# EIT_Recorder.net
KiCad netlist of a schematic drawn in EAGLE
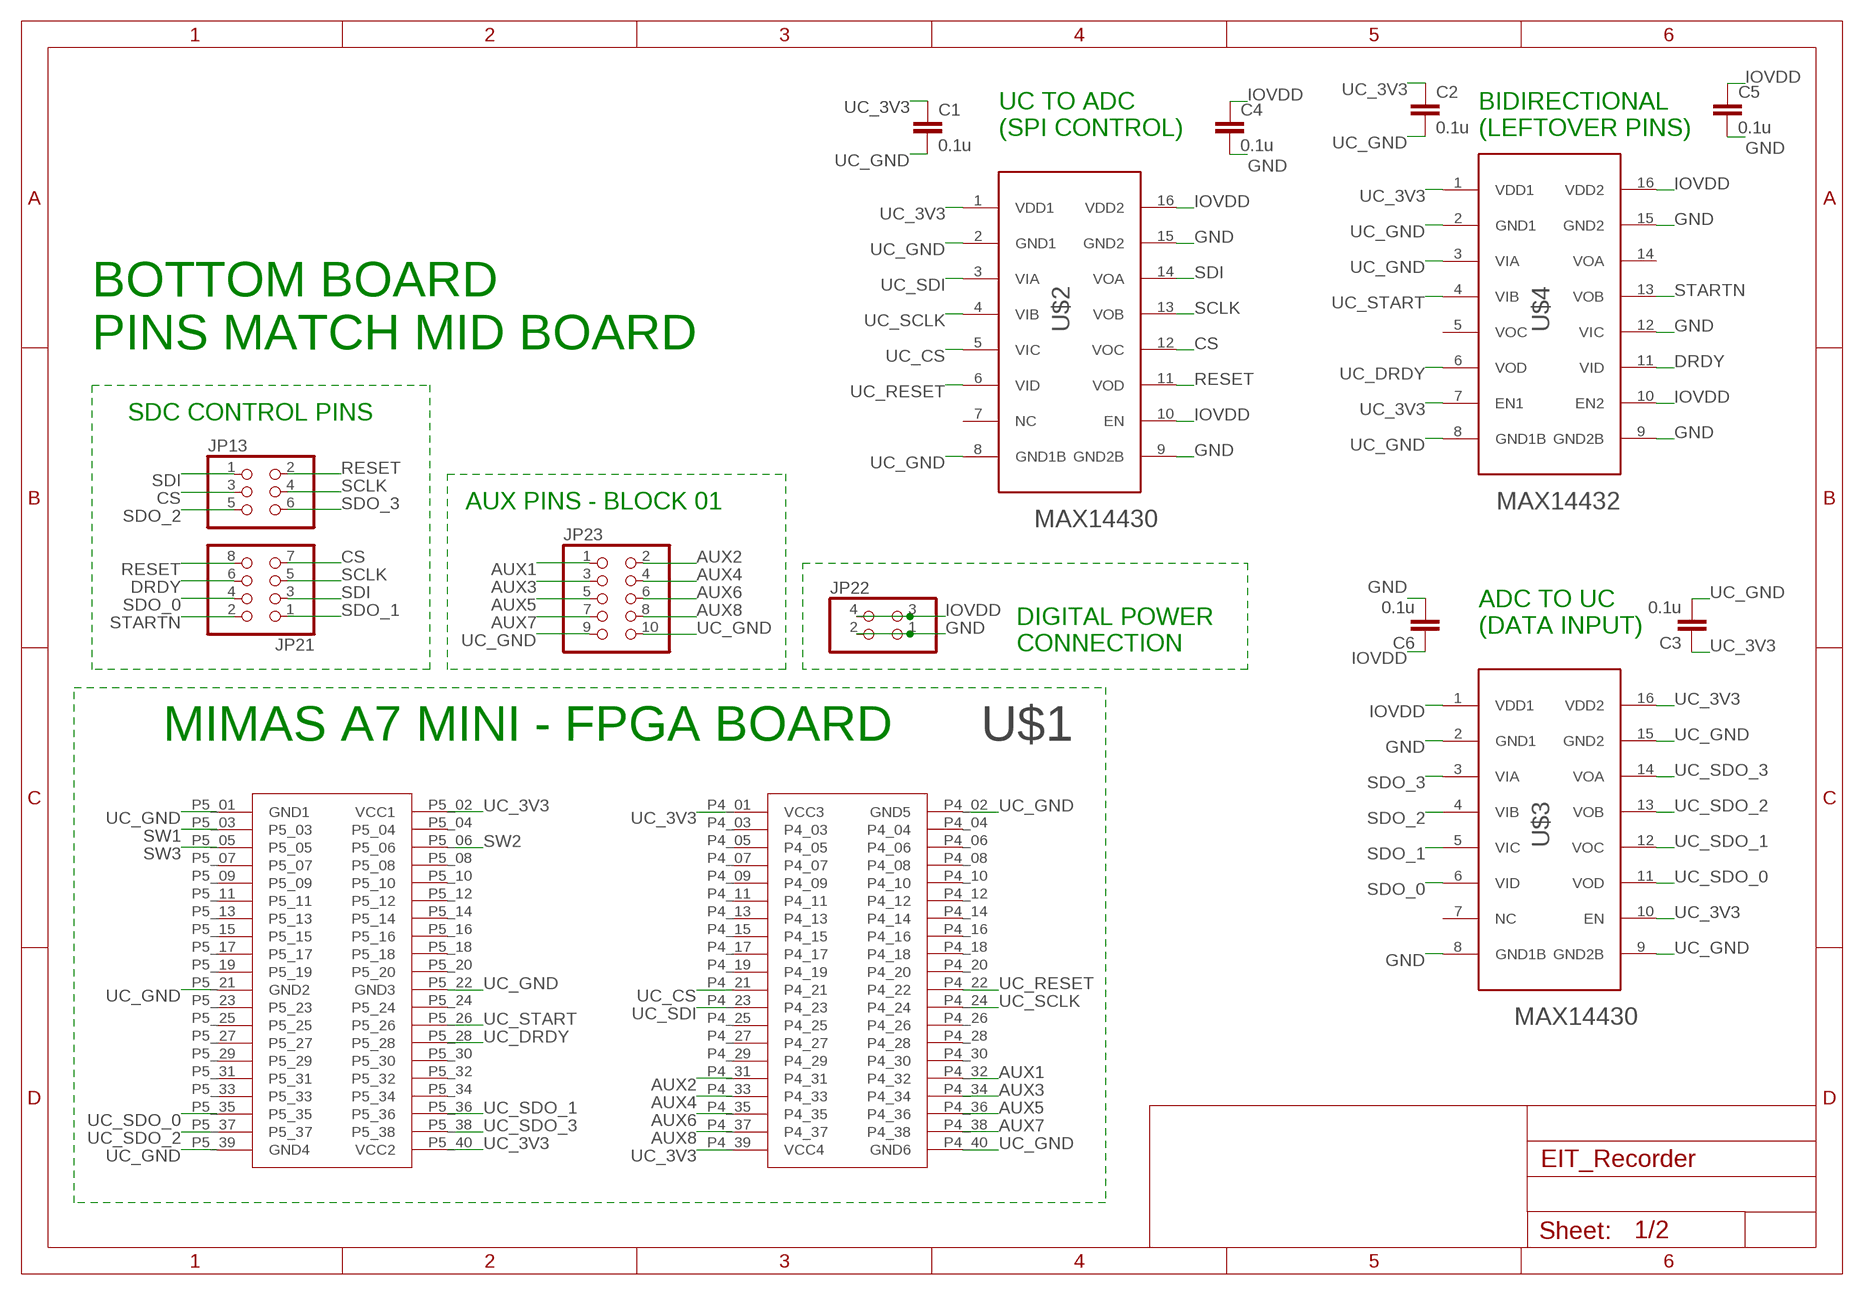
[diagram p0: schematic, sheet 1]
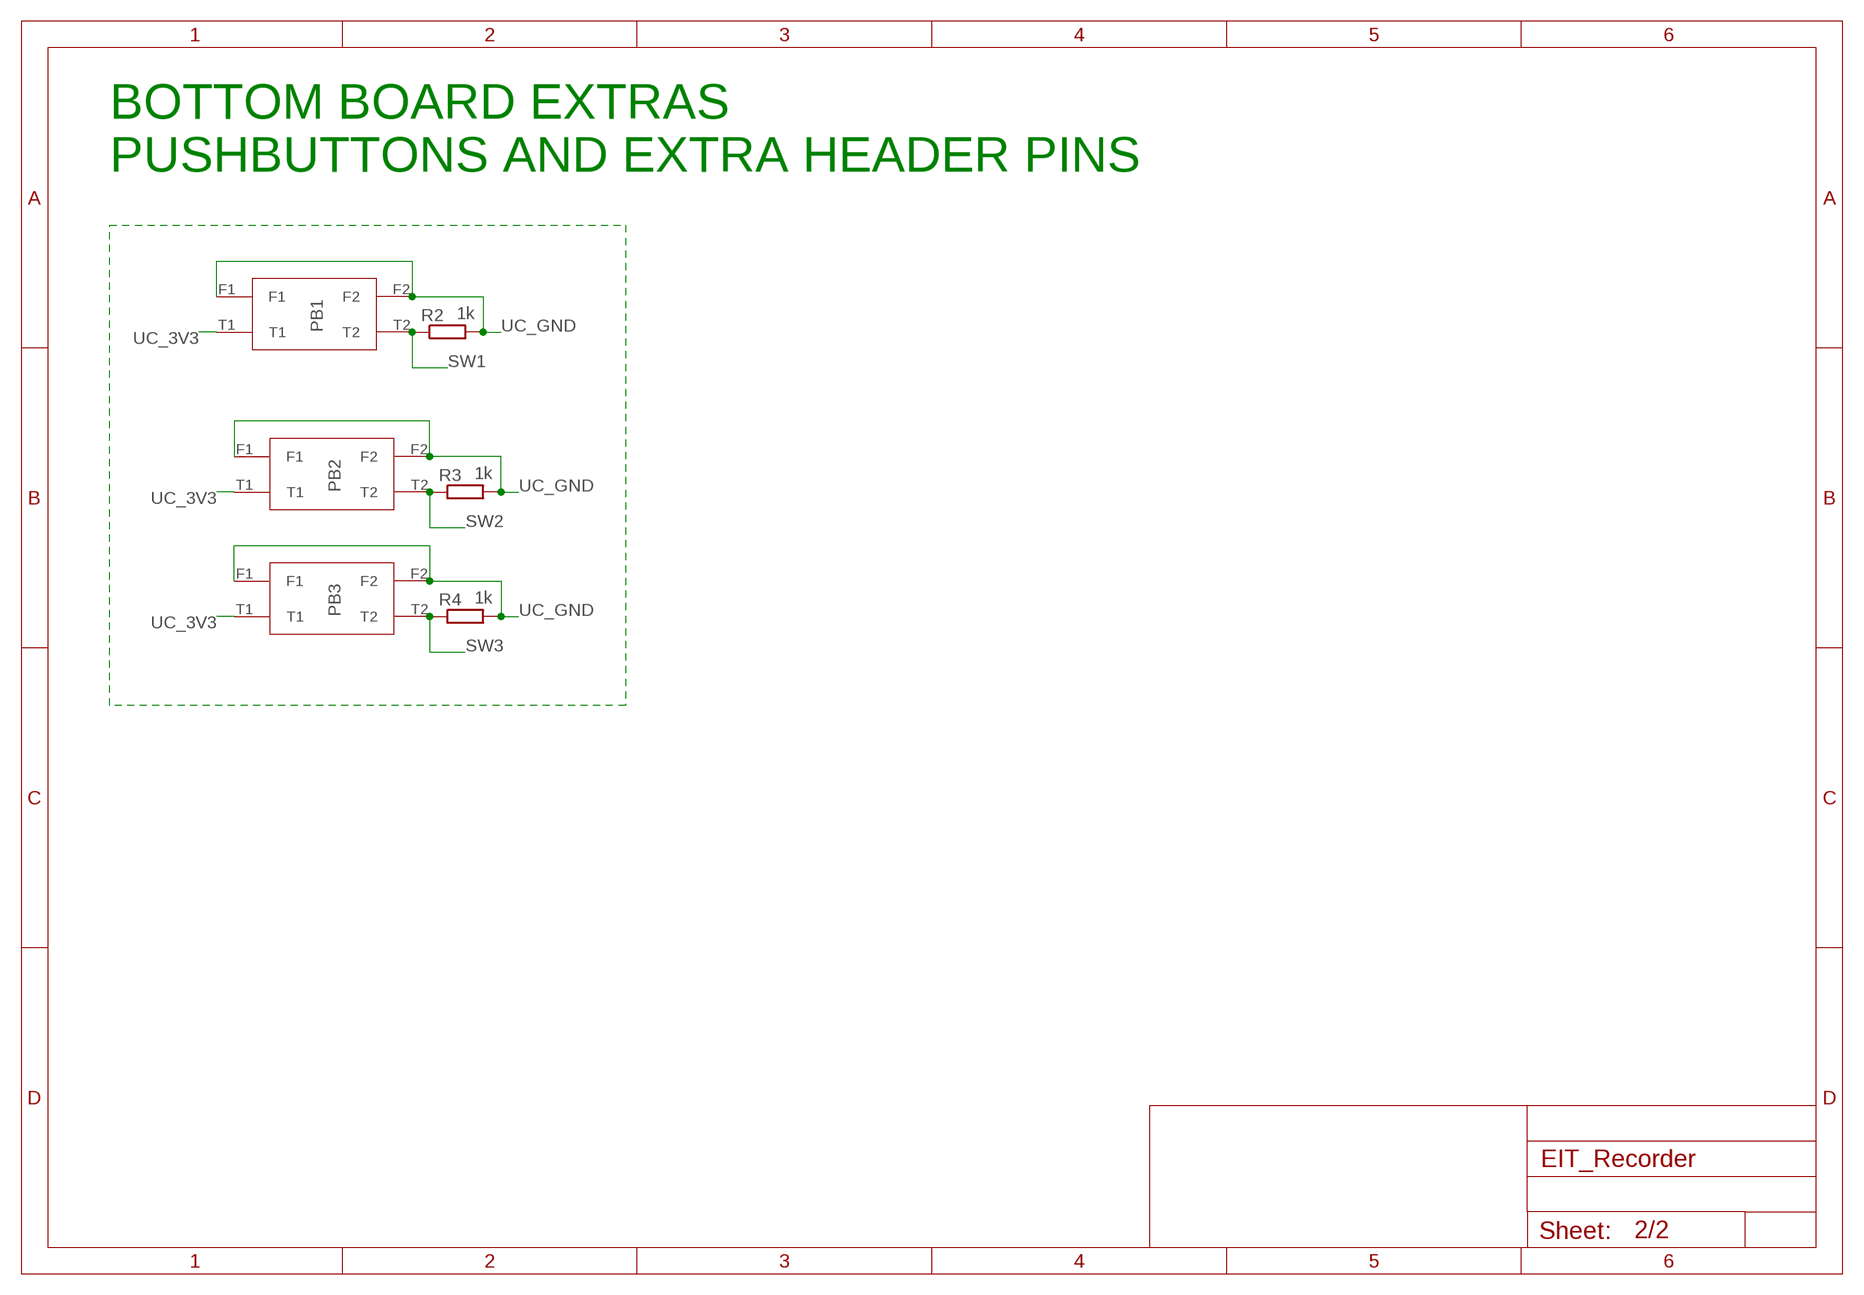
[diagram p1: schematic, sheet 2]

(export (version "E")
  (design (tool "Eeschema 10.0.6"))
  (components
    (comp (ref "PB1")
      (value "PUSHBUTTON_95C06B2RAT")
      (footprint "eagle-import:PUSHBUTTON_95C06B2RAT")
      (libsource (lib "eagle-import") (part "PUSHBUTTON_95C06B2RAT"))
    )
    (comp (ref "PB2")
      (value "PUSHBUTTON_95C06B2RAT")
      (footprint "eagle-import:PUSHBUTTON_95C06B2RAT")
      (libsource (lib "eagle-import") (part "PUSHBUTTON_95C06B2RAT"))
    )
    (comp (ref "PB3")
      (value "PUSHBUTTON_95C06B2RAT")
      (footprint "eagle-import:PUSHBUTTON_95C06B2RAT")
      (libsource (lib "eagle-import") (part "PUSHBUTTON_95C06B2RAT"))
    )
    (comp (ref "R2")
      (value "1k")
      (footprint "eagle-import:R0805")
      (libsource (lib "eagle-import") (part "R-EU_R0805"))
    )
    (comp (ref "R3")
      (value "1k")
      (footprint "eagle-import:R0805")
      (libsource (lib "eagle-import") (part "R-EU_R0805"))
    )
    (comp (ref "R4")
      (value "1k")
      (footprint "eagle-import:R0805")
      (libsource (lib "eagle-import") (part "R-EU_R0805"))
    )
    (comp (ref "C1")
      (value "0.1u")
      (footprint "eagle-import:C0805")
      (libsource (lib "eagle-import") (part "C-EUC0805"))
    )
    (comp (ref "C2")
      (value "0.1u")
      (footprint "eagle-import:C0805")
      (libsource (lib "eagle-import") (part "C-EUC0805"))
    )
    (comp (ref "C3")
      (value "0.1u")
      (footprint "eagle-import:C0805")
      (libsource (lib "eagle-import") (part "C-EUC0805"))
    )
    (comp (ref "C4")
      (value "0.1u")
      (footprint "eagle-import:C0805")
      (libsource (lib "eagle-import") (part "C-EUC0805"))
    )
    (comp (ref "C5")
      (value "0.1u")
      (footprint "eagle-import:C0805")
      (libsource (lib "eagle-import") (part "C-EUC0805"))
    )
    (comp (ref "C6")
      (value "0.1u")
      (footprint "eagle-import:C0805")
      (libsource (lib "eagle-import") (part "C-EUC0805"))
    )
    (comp (ref "JP13")
      (value "PINHD-2X3")
      (footprint "eagle-import:2X03")
      (libsource (lib "eagle-import") (part "PINHD-2X3"))
    )
    (comp (ref "JP21")
      (value "PINHD-2X4")
      (footprint "eagle-import:2X04")
      (libsource (lib "eagle-import") (part "PINHD-2X4"))
    )
    (comp (ref "JP22")
      (value "PINHD-2X2")
      (footprint "eagle-import:2X02")
      (libsource (lib "eagle-import") (part "PINHD-2X2"))
    )
    (comp (ref "JP23")
      (value "PINHD-2X5/90")
      (footprint "eagle-import:2X05_90")
      (libsource (lib "eagle-import") (part "PINHD-2X5/90"))
    )
    (comp (ref "U$1")
      (value "MIMAS_A7_MINI")
      (footprint "eagle-import:MIMAS_A7_MINI")
      (libsource (lib "eagle-import") (part "MIMAS_A7_MINI"))
    )
    (comp (ref "U$2")
      (value "MAX14430")
      (footprint "eagle-import:SOIC16_CUSTOM")
      (libsource (lib "eagle-import") (part "MAX14430"))
    )
    (comp (ref "U$3")
      (value "MAX14430")
      (footprint "eagle-import:SOIC16_CUSTOM")
      (libsource (lib "eagle-import") (part "MAX14430"))
    )
    (comp (ref "U$4")
      (value "MAX14432")
      (footprint "eagle-import:SOIC16_CUSTOM")
      (libsource (lib "eagle-import") (part "MAX14432"))
    )
  )
  (nets
    (net (code "1") (name "AUX1") (class "Default")
      (node (ref "JP23") (pin "1") (pinfunction "1_1") (pintype "passive"))
      (node (ref "U$1") (pin "P4_32") (pinfunction "P4_32_P4_32") (pintype "bidirectional"))
    )
    (net (code "2") (name "AUX2") (class "Default")
      (node (ref "JP23") (pin "2") (pinfunction "2_2") (pintype "passive"))
      (node (ref "U$1") (pin "P4_31") (pinfunction "P4_31_P4_31") (pintype "bidirectional"))
    )
    (net (code "3") (name "AUX3") (class "Default")
      (node (ref "JP23") (pin "3") (pinfunction "3_3") (pintype "passive"))
      (node (ref "U$1") (pin "P4_34") (pinfunction "P4_34_P4_34") (pintype "bidirectional"))
    )
    (net (code "4") (name "AUX4") (class "Default")
      (node (ref "JP23") (pin "4") (pinfunction "4_4") (pintype "passive"))
      (node (ref "U$1") (pin "P4_33") (pinfunction "P4_33_P4_33") (pintype "bidirectional"))
    )
    (net (code "5") (name "AUX5") (class "Default")
      (node (ref "JP23") (pin "5") (pinfunction "5_5") (pintype "passive"))
      (node (ref "U$1") (pin "P4_36") (pinfunction "P4_36_P4_36") (pintype "bidirectional"))
    )
    (net (code "6") (name "AUX6") (class "Default")
      (node (ref "JP23") (pin "6") (pinfunction "6_6") (pintype "passive"))
      (node (ref "U$1") (pin "P4_35") (pinfunction "P4_35_P4_35") (pintype "bidirectional"))
    )
    (net (code "7") (name "AUX7") (class "Default")
      (node (ref "JP23") (pin "7") (pinfunction "7_7") (pintype "passive"))
      (node (ref "U$1") (pin "P4_38") (pinfunction "P4_38_P4_38") (pintype "bidirectional"))
    )
    (net (code "8") (name "AUX8") (class "Default")
      (node (ref "JP23") (pin "8") (pinfunction "8_8") (pintype "passive"))
      (node (ref "U$1") (pin "P4_37") (pinfunction "P4_37_P4_37") (pintype "bidirectional"))
    )
    (net (code "9") (name "CS") (class "Default")
      (node (ref "JP13") (pin "3") (pinfunction "3_3") (pintype "passive"))
      (node (ref "JP21") (pin "7") (pinfunction "7_7") (pintype "passive"))
      (node (ref "U$2") (pin "12") (pinfunction "VOC_12") (pintype "output"))
    )
    (net (code "10") (name "DRDY") (class "Default")
      (node (ref "JP21") (pin "6") (pinfunction "6_6") (pintype "passive"))
      (node (ref "U$4") (pin "11") (pinfunction "VID_11") (pintype "input"))
    )
    (net (code "11") (name "GND") (class "Default")
      (node (ref "C4") (pin "2") (pinfunction "2_2") (pintype "passive"))
      (node (ref "C5") (pin "2") (pinfunction "2_2") (pintype "passive"))
      (node (ref "C6") (pin "2") (pinfunction "2_2") (pintype "passive"))
      (node (ref "JP22") (pin "1") (pinfunction "1_1") (pintype "passive"))
      (node (ref "JP22") (pin "2") (pinfunction "2_2") (pintype "passive"))
      (node (ref "U$2") (pin "15") (pinfunction "GND2_15") (pintype "power_in"))
      (node (ref "U$2") (pin "9") (pinfunction "GND2B_9") (pintype "power_in"))
      (node (ref "U$3") (pin "2") (pinfunction "GND1_2") (pintype "power_in"))
      (node (ref "U$3") (pin "8") (pinfunction "GND1B_8") (pintype "power_in"))
      (node (ref "U$4") (pin "12") (pinfunction "VIC_12") (pintype "input"))
      (node (ref "U$4") (pin "15") (pinfunction "GND2_15") (pintype "power_in"))
      (node (ref "U$4") (pin "9") (pinfunction "GND2B_9") (pintype "power_in"))
    )
    (net (code "12") (name "IOVDD") (class "Default")
      (node (ref "C4") (pin "1") (pinfunction "1_1") (pintype "passive"))
      (node (ref "C5") (pin "1") (pinfunction "1_1") (pintype "passive"))
      (node (ref "C6") (pin "1") (pinfunction "1_1") (pintype "passive"))
      (node (ref "JP22") (pin "3") (pinfunction "3_3") (pintype "passive"))
      (node (ref "JP22") (pin "4") (pinfunction "4_4") (pintype "passive"))
      (node (ref "U$2") (pin "10") (pinfunction "EN_10") (pintype "bidirectional"))
      (node (ref "U$2") (pin "16") (pinfunction "VDD2_16") (pintype "power_in"))
      (node (ref "U$3") (pin "1") (pinfunction "VDD1_1") (pintype "power_in"))
      (node (ref "U$4") (pin "10") (pinfunction "EN2_10") (pintype "bidirectional"))
      (node (ref "U$4") (pin "16") (pinfunction "VDD2_16") (pintype "power_in"))
    )
    (net (code "13") (name "RESET") (class "Default")
      (node (ref "JP13") (pin "2") (pinfunction "2_2") (pintype "passive"))
      (node (ref "JP21") (pin "8") (pinfunction "8_8") (pintype "passive"))
      (node (ref "U$2") (pin "11") (pinfunction "VOD_11") (pintype "output"))
    )
    (net (code "14") (name "SCLK") (class "Default")
      (node (ref "JP13") (pin "4") (pinfunction "4_4") (pintype "passive"))
      (node (ref "JP21") (pin "5") (pinfunction "5_5") (pintype "passive"))
      (node (ref "U$2") (pin "13") (pinfunction "VOB_13") (pintype "output"))
    )
    (net (code "15") (name "SDI") (class "Default")
      (node (ref "JP13") (pin "1") (pinfunction "1_1") (pintype "passive"))
      (node (ref "JP21") (pin "3") (pinfunction "3_3") (pintype "passive"))
      (node (ref "U$2") (pin "14") (pinfunction "VOA_14") (pintype "output"))
    )
    (net (code "16") (name "SDO_0") (class "Default")
      (node (ref "JP21") (pin "4") (pinfunction "4_4") (pintype "passive"))
      (node (ref "U$3") (pin "6") (pinfunction "VID_6") (pintype "input"))
    )
    (net (code "17") (name "SDO_1") (class "Default")
      (node (ref "JP21") (pin "1") (pinfunction "1_1") (pintype "passive"))
      (node (ref "U$3") (pin "5") (pinfunction "VIC_5") (pintype "input"))
    )
    (net (code "18") (name "SDO_2") (class "Default")
      (node (ref "JP13") (pin "5") (pinfunction "5_5") (pintype "passive"))
      (node (ref "U$3") (pin "4") (pinfunction "VIB_4") (pintype "input"))
    )
    (net (code "19") (name "SDO_3") (class "Default")
      (node (ref "JP13") (pin "6") (pinfunction "6_6") (pintype "passive"))
      (node (ref "U$3") (pin "3") (pinfunction "VIA_3") (pintype "input"))
    )
    (net (code "20") (name "STARTN") (class "Default")
      (node (ref "JP21") (pin "2") (pinfunction "2_2") (pintype "passive"))
      (node (ref "U$4") (pin "13") (pinfunction "VOB_13") (pintype "output"))
    )
    (net (code "21") (name "SW1") (class "Default")
      (node (ref "PB1") (pin "T2") (pinfunction "T2_T2") (pintype "bidirectional"))
      (node (ref "R2") (pin "1") (pinfunction "1_1") (pintype "passive"))
      (node (ref "U$1") (pin "P5_03") (pinfunction "P5_03_P5_03") (pintype "bidirectional"))
    )
    (net (code "22") (name "SW2") (class "Default")
      (node (ref "PB2") (pin "T2") (pinfunction "T2_T2") (pintype "bidirectional"))
      (node (ref "R3") (pin "1") (pinfunction "1_1") (pintype "passive"))
      (node (ref "U$1") (pin "P5_06") (pinfunction "P5_06_P5_06") (pintype "bidirectional"))
    )
    (net (code "23") (name "SW3") (class "Default")
      (node (ref "PB3") (pin "T2") (pinfunction "T2_T2") (pintype "bidirectional"))
      (node (ref "R4") (pin "1") (pinfunction "1_1") (pintype "passive"))
      (node (ref "U$1") (pin "P5_05") (pinfunction "P5_05_P5_05") (pintype "bidirectional"))
    )
    (net (code "24") (name "UC_3V3") (class "Default")
      (node (ref "C1") (pin "1") (pinfunction "1_1") (pintype "passive"))
      (node (ref "C2") (pin "1") (pinfunction "1_1") (pintype "passive"))
      (node (ref "C3") (pin "1") (pinfunction "1_1") (pintype "passive"))
      (node (ref "PB1") (pin "T1") (pinfunction "T1_T1") (pintype "bidirectional"))
      (node (ref "PB2") (pin "T1") (pinfunction "T1_T1") (pintype "bidirectional"))
      (node (ref "PB3") (pin "T1") (pinfunction "T1_T1") (pintype "bidirectional"))
      (node (ref "U$1") (pin "P4_01") (pinfunction "VCC3_P4_01") (pintype "power_in"))
      (node (ref "U$1") (pin "P4_39") (pinfunction "VCC4_P4_39") (pintype "power_in"))
      (node (ref "U$1") (pin "P5_02") (pinfunction "VCC1_P5_02") (pintype "power_in"))
      (node (ref "U$1") (pin "P5_40") (pinfunction "VCC2_P5_40") (pintype "power_in"))
      (node (ref "U$2") (pin "1") (pinfunction "VDD1_1") (pintype "power_in"))
      (node (ref "U$3") (pin "10") (pinfunction "EN_10") (pintype "bidirectional"))
      (node (ref "U$3") (pin "16") (pinfunction "VDD2_16") (pintype "power_in"))
      (node (ref "U$4") (pin "1") (pinfunction "VDD1_1") (pintype "power_in"))
      (node (ref "U$4") (pin "7") (pinfunction "EN1_7") (pintype "input"))
    )
    (net (code "25") (name "UC_CS") (class "Default")
      (node (ref "U$1") (pin "P4_21") (pinfunction "P4_21_P4_21") (pintype "bidirectional"))
      (node (ref "U$2") (pin "5") (pinfunction "VIC_5") (pintype "input"))
    )
    (net (code "26") (name "UC_DRDY") (class "Default")
      (node (ref "U$1") (pin "P5_28") (pinfunction "P5_28_P5_28") (pintype "bidirectional"))
      (node (ref "U$4") (pin "6") (pinfunction "VOD_6") (pintype "output"))
    )
    (net (code "27") (name "UC_GND") (class "Default")
      (node (ref "C1") (pin "2") (pinfunction "2_2") (pintype "passive"))
      (node (ref "C2") (pin "2") (pinfunction "2_2") (pintype "passive"))
      (node (ref "C3") (pin "2") (pinfunction "2_2") (pintype "passive"))
      (node (ref "JP23") (pin "10") (pinfunction "10_10") (pintype "passive"))
      (node (ref "JP23") (pin "9") (pinfunction "9_9") (pintype "passive"))
      (node (ref "PB1") (pin "F1") (pinfunction "F1_F1") (pintype "bidirectional"))
      (node (ref "PB1") (pin "F2") (pinfunction "F2_F2") (pintype "bidirectional"))
      (node (ref "PB2") (pin "F1") (pinfunction "F1_F1") (pintype "bidirectional"))
      (node (ref "PB2") (pin "F2") (pinfunction "F2_F2") (pintype "bidirectional"))
      (node (ref "PB3") (pin "F1") (pinfunction "F1_F1") (pintype "bidirectional"))
      (node (ref "PB3") (pin "F2") (pinfunction "F2_F2") (pintype "bidirectional"))
      (node (ref "R2") (pin "2") (pinfunction "2_2") (pintype "passive"))
      (node (ref "R3") (pin "2") (pinfunction "2_2") (pintype "passive"))
      (node (ref "R4") (pin "2") (pinfunction "2_2") (pintype "passive"))
      (node (ref "U$1") (pin "P4_02") (pinfunction "GND5_P4_02") (pintype "passive"))
      (node (ref "U$1") (pin "P4_40") (pinfunction "GND6_P4_40") (pintype "passive"))
      (node (ref "U$1") (pin "P5_01") (pinfunction "GND1_P5_01") (pintype "passive"))
      (node (ref "U$1") (pin "P5_21") (pinfunction "GND2_P5_21") (pintype "passive"))
      (node (ref "U$1") (pin "P5_22") (pinfunction "GND3_P5_22") (pintype "passive"))
      (node (ref "U$1") (pin "P5_39") (pinfunction "GND4_P5_39") (pintype "passive"))
      (node (ref "U$2") (pin "2") (pinfunction "GND1_2") (pintype "power_in"))
      (node (ref "U$2") (pin "8") (pinfunction "GND1B_8") (pintype "power_in"))
      (node (ref "U$3") (pin "15") (pinfunction "GND2_15") (pintype "power_in"))
      (node (ref "U$3") (pin "9") (pinfunction "GND2B_9") (pintype "power_in"))
      (node (ref "U$4") (pin "2") (pinfunction "GND1_2") (pintype "power_in"))
      (node (ref "U$4") (pin "3") (pinfunction "VIA_3") (pintype "input"))
      (node (ref "U$4") (pin "8") (pinfunction "GND1B_8") (pintype "power_in"))
    )
    (net (code "28") (name "UC_RESET") (class "Default")
      (node (ref "U$1") (pin "P4_22") (pinfunction "P4_22_P4_22") (pintype "bidirectional"))
      (node (ref "U$2") (pin "6") (pinfunction "VID_6") (pintype "input"))
    )
    (net (code "29") (name "UC_SCLK") (class "Default")
      (node (ref "U$1") (pin "P4_24") (pinfunction "P4_24_P4_24") (pintype "bidirectional"))
      (node (ref "U$2") (pin "4") (pinfunction "VIB_4") (pintype "input"))
    )
    (net (code "30") (name "UC_SDI") (class "Default")
      (node (ref "U$1") (pin "P4_23") (pinfunction "P4_23_P4_23") (pintype "bidirectional"))
      (node (ref "U$2") (pin "3") (pinfunction "VIA_3") (pintype "input"))
    )
    (net (code "31") (name "UC_SDO_0") (class "Default")
      (node (ref "U$1") (pin "P5_35") (pinfunction "P5_35_P5_35") (pintype "bidirectional"))
      (node (ref "U$3") (pin "11") (pinfunction "VOD_11") (pintype "output"))
    )
    (net (code "32") (name "UC_SDO_1") (class "Default")
      (node (ref "U$1") (pin "P5_36") (pinfunction "P5_36_P5_36") (pintype "bidirectional"))
      (node (ref "U$3") (pin "12") (pinfunction "VOC_12") (pintype "output"))
    )
    (net (code "33") (name "UC_SDO_2") (class "Default")
      (node (ref "U$1") (pin "P5_37") (pinfunction "P5_37_P5_37") (pintype "bidirectional"))
      (node (ref "U$3") (pin "13") (pinfunction "VOB_13") (pintype "output"))
    )
    (net (code "34") (name "UC_SDO_3") (class "Default")
      (node (ref "U$1") (pin "P5_38") (pinfunction "P5_38_P5_38") (pintype "bidirectional"))
      (node (ref "U$3") (pin "14") (pinfunction "VOA_14") (pintype "output"))
    )
    (net (code "35") (name "UC_START") (class "Default")
      (node (ref "U$1") (pin "P5_26") (pinfunction "P5_26_P5_26") (pintype "bidirectional"))
      (node (ref "U$4") (pin "4") (pinfunction "VIB_4") (pintype "input"))
    )
    (net (code "36") (name "unconnected-(U$1-PadP4_03)") (class "Default")
      (node (ref "U$1") (pin "P4_03") (pinfunction "P4_03_P4_03") (pintype "bidirectional"))
    )
    (net (code "37") (name "unconnected-(U$1-PadP4_04)") (class "Default")
      (node (ref "U$1") (pin "P4_04") (pinfunction "P4_04_P4_04") (pintype "bidirectional"))
    )
    (net (code "38") (name "unconnected-(U$1-PadP4_05)") (class "Default")
      (node (ref "U$1") (pin "P4_05") (pinfunction "P4_05_P4_05") (pintype "bidirectional"))
    )
    (net (code "39") (name "unconnected-(U$1-PadP4_06)") (class "Default")
      (node (ref "U$1") (pin "P4_06") (pinfunction "P4_06_P4_06") (pintype "bidirectional"))
    )
    (net (code "40") (name "unconnected-(U$1-PadP4_07)") (class "Default")
      (node (ref "U$1") (pin "P4_07") (pinfunction "P4_07_P4_07") (pintype "bidirectional"))
    )
    (net (code "41") (name "unconnected-(U$1-PadP4_08)") (class "Default")
      (node (ref "U$1") (pin "P4_08") (pinfunction "P4_08_P4_08") (pintype "bidirectional"))
    )
    (net (code "42") (name "unconnected-(U$1-PadP4_09)") (class "Default")
      (node (ref "U$1") (pin "P4_09") (pinfunction "P4_09_P4_09") (pintype "bidirectional"))
    )
    (net (code "43") (name "unconnected-(U$1-PadP4_10)") (class "Default")
      (node (ref "U$1") (pin "P4_10") (pinfunction "P4_10_P4_10") (pintype "bidirectional"))
    )
    (net (code "44") (name "unconnected-(U$1-PadP4_11)") (class "Default")
      (node (ref "U$1") (pin "P4_11") (pinfunction "P4_11_P4_11") (pintype "bidirectional"))
    )
    (net (code "45") (name "unconnected-(U$1-PadP4_12)") (class "Default")
      (node (ref "U$1") (pin "P4_12") (pinfunction "P4_12_P4_12") (pintype "bidirectional"))
    )
    (net (code "46") (name "unconnected-(U$1-PadP4_13)") (class "Default")
      (node (ref "U$1") (pin "P4_13") (pinfunction "P4_13_P4_13") (pintype "bidirectional"))
    )
    (net (code "47") (name "unconnected-(U$1-PadP4_14)") (class "Default")
      (node (ref "U$1") (pin "P4_14") (pinfunction "P4_14_P4_14") (pintype "bidirectional"))
    )
    (net (code "48") (name "unconnected-(U$1-PadP4_15)") (class "Default")
      (node (ref "U$1") (pin "P4_15") (pinfunction "P4_15_P4_15") (pintype "bidirectional"))
    )
    (net (code "49") (name "unconnected-(U$1-PadP4_16)") (class "Default")
      (node (ref "U$1") (pin "P4_16") (pinfunction "P4_16_P4_16") (pintype "bidirectional"))
    )
    (net (code "50") (name "unconnected-(U$1-PadP4_17)") (class "Default")
      (node (ref "U$1") (pin "P4_17") (pinfunction "P4_17_P4_17") (pintype "bidirectional"))
    )
    (net (code "51") (name "unconnected-(U$1-PadP4_18)") (class "Default")
      (node (ref "U$1") (pin "P4_18") (pinfunction "P4_18_P4_18") (pintype "bidirectional"))
    )
    (net (code "52") (name "unconnected-(U$1-PadP4_19)") (class "Default")
      (node (ref "U$1") (pin "P4_19") (pinfunction "P4_19_P4_19") (pintype "bidirectional"))
    )
    (net (code "53") (name "unconnected-(U$1-PadP4_20)") (class "Default")
      (node (ref "U$1") (pin "P4_20") (pinfunction "P4_20_P4_20") (pintype "bidirectional"))
    )
    (net (code "54") (name "unconnected-(U$1-PadP4_25)") (class "Default")
      (node (ref "U$1") (pin "P4_25") (pinfunction "P4_25_P4_25") (pintype "bidirectional"))
    )
    (net (code "55") (name "unconnected-(U$1-PadP4_26)") (class "Default")
      (node (ref "U$1") (pin "P4_26") (pinfunction "P4_26_P4_26") (pintype "bidirectional"))
    )
    (net (code "56") (name "unconnected-(U$1-PadP4_27)") (class "Default")
      (node (ref "U$1") (pin "P4_27") (pinfunction "P4_27_P4_27") (pintype "bidirectional"))
    )
    (net (code "57") (name "unconnected-(U$1-PadP4_28)") (class "Default")
      (node (ref "U$1") (pin "P4_28") (pinfunction "P4_28_P4_28") (pintype "bidirectional"))
    )
    (net (code "58") (name "unconnected-(U$1-PadP4_29)") (class "Default")
      (node (ref "U$1") (pin "P4_29") (pinfunction "P4_29_P4_29") (pintype "bidirectional"))
    )
    (net (code "59") (name "unconnected-(U$1-PadP4_30)") (class "Default")
      (node (ref "U$1") (pin "P4_30") (pinfunction "P4_30_P4_30") (pintype "bidirectional"))
    )
    (net (code "60") (name "unconnected-(U$1-PadP5_04)") (class "Default")
      (node (ref "U$1") (pin "P5_04") (pinfunction "P5_04_P5_04") (pintype "bidirectional"))
    )
    (net (code "61") (name "unconnected-(U$1-PadP5_07)") (class "Default")
      (node (ref "U$1") (pin "P5_07") (pinfunction "P5_07_P5_07") (pintype "bidirectional"))
    )
    (net (code "62") (name "unconnected-(U$1-PadP5_08)") (class "Default")
      (node (ref "U$1") (pin "P5_08") (pinfunction "P5_08_P5_08") (pintype "bidirectional"))
    )
    (net (code "63") (name "unconnected-(U$1-PadP5_09)") (class "Default")
      (node (ref "U$1") (pin "P5_09") (pinfunction "P5_09_P5_09") (pintype "bidirectional"))
    )
    (net (code "64") (name "unconnected-(U$1-PadP5_10)") (class "Default")
      (node (ref "U$1") (pin "P5_10") (pinfunction "P5_10_P5_10") (pintype "bidirectional"))
    )
    (net (code "65") (name "unconnected-(U$1-PadP5_11)") (class "Default")
      (node (ref "U$1") (pin "P5_11") (pinfunction "P5_11_P5_11") (pintype "bidirectional"))
    )
    (net (code "66") (name "unconnected-(U$1-PadP5_12)") (class "Default")
      (node (ref "U$1") (pin "P5_12") (pinfunction "P5_12_P5_12") (pintype "bidirectional"))
    )
    (net (code "67") (name "unconnected-(U$1-PadP5_13)") (class "Default")
      (node (ref "U$1") (pin "P5_13") (pinfunction "P5_13_P5_13") (pintype "bidirectional"))
    )
    (net (code "68") (name "unconnected-(U$1-PadP5_14)") (class "Default")
      (node (ref "U$1") (pin "P5_14") (pinfunction "P5_14_P5_14") (pintype "bidirectional"))
    )
    (net (code "69") (name "unconnected-(U$1-PadP5_15)") (class "Default")
      (node (ref "U$1") (pin "P5_15") (pinfunction "P5_15_P5_15") (pintype "bidirectional"))
    )
    (net (code "70") (name "unconnected-(U$1-PadP5_16)") (class "Default")
      (node (ref "U$1") (pin "P5_16") (pinfunction "P5_16_P5_16") (pintype "bidirectional"))
    )
    (net (code "71") (name "unconnected-(U$1-PadP5_17)") (class "Default")
      (node (ref "U$1") (pin "P5_17") (pinfunction "P5_17_P5_17") (pintype "bidirectional"))
    )
    (net (code "72") (name "unconnected-(U$1-PadP5_18)") (class "Default")
      (node (ref "U$1") (pin "P5_18") (pinfunction "P5_18_P5_18") (pintype "bidirectional"))
    )
    (net (code "73") (name "unconnected-(U$1-PadP5_19)") (class "Default")
      (node (ref "U$1") (pin "P5_19") (pinfunction "P5_19_P5_19") (pintype "bidirectional"))
    )
    (net (code "74") (name "unconnected-(U$1-PadP5_20)") (class "Default")
      (node (ref "U$1") (pin "P5_20") (pinfunction "P5_20_P5_20") (pintype "bidirectional"))
    )
    (net (code "75") (name "unconnected-(U$1-PadP5_23)") (class "Default")
      (node (ref "U$1") (pin "P5_23") (pinfunction "P5_23_P5_23") (pintype "bidirectional"))
    )
    (net (code "76") (name "unconnected-(U$1-PadP5_24)") (class "Default")
      (node (ref "U$1") (pin "P5_24") (pinfunction "P5_24_P5_24") (pintype "bidirectional"))
    )
    (net (code "77") (name "unconnected-(U$1-PadP5_25)") (class "Default")
      (node (ref "U$1") (pin "P5_25") (pinfunction "P5_25_P5_25") (pintype "bidirectional"))
    )
    (net (code "78") (name "unconnected-(U$1-PadP5_27)") (class "Default")
      (node (ref "U$1") (pin "P5_27") (pinfunction "P5_27_P5_27") (pintype "bidirectional"))
    )
    (net (code "79") (name "unconnected-(U$1-PadP5_29)") (class "Default")
      (node (ref "U$1") (pin "P5_29") (pinfunction "P5_29_P5_29") (pintype "bidirectional"))
    )
    (net (code "80") (name "unconnected-(U$1-PadP5_30)") (class "Default")
      (node (ref "U$1") (pin "P5_30") (pinfunction "P5_30_P5_30") (pintype "bidirectional"))
    )
    (net (code "81") (name "unconnected-(U$1-PadP5_31)") (class "Default")
      (node (ref "U$1") (pin "P5_31") (pinfunction "P5_31_P5_31") (pintype "bidirectional"))
    )
    (net (code "82") (name "unconnected-(U$1-PadP5_32)") (class "Default")
      (node (ref "U$1") (pin "P5_32") (pinfunction "P5_32_P5_32") (pintype "bidirectional"))
    )
    (net (code "83") (name "unconnected-(U$1-PadP5_33)") (class "Default")
      (node (ref "U$1") (pin "P5_33") (pinfunction "P5_33_P5_33") (pintype "bidirectional"))
    )
    (net (code "84") (name "unconnected-(U$1-PadP5_34)") (class "Default")
      (node (ref "U$1") (pin "P5_34") (pinfunction "P5_34_P5_34") (pintype "bidirectional"))
    )
    (net (code "85") (name "unconnected-(U$2-NC-Pad7)") (class "Default")
      (node (ref "U$2") (pin "7") (pinfunction "NC_7") (pintype "no_connect"))
    )
    (net (code "86") (name "unconnected-(U$3-NC-Pad7)") (class "Default")
      (node (ref "U$3") (pin "7") (pinfunction "NC_7") (pintype "no_connect"))
    )
    (net (code "87") (name "unconnected-(U$4-VOA-Pad14)") (class "Default")
      (node (ref "U$4") (pin "14") (pinfunction "VOA_14") (pintype "output"))
    )
    (net (code "88") (name "unconnected-(U$4-VOC-Pad5)") (class "Default")
      (node (ref "U$4") (pin "5") (pinfunction "VOC_5") (pintype "output"))
    )
  )
)
